# SCH_NSL-23-24_2023-12-20.net
KiCad netlist of a schematic drawn in EasyEDA
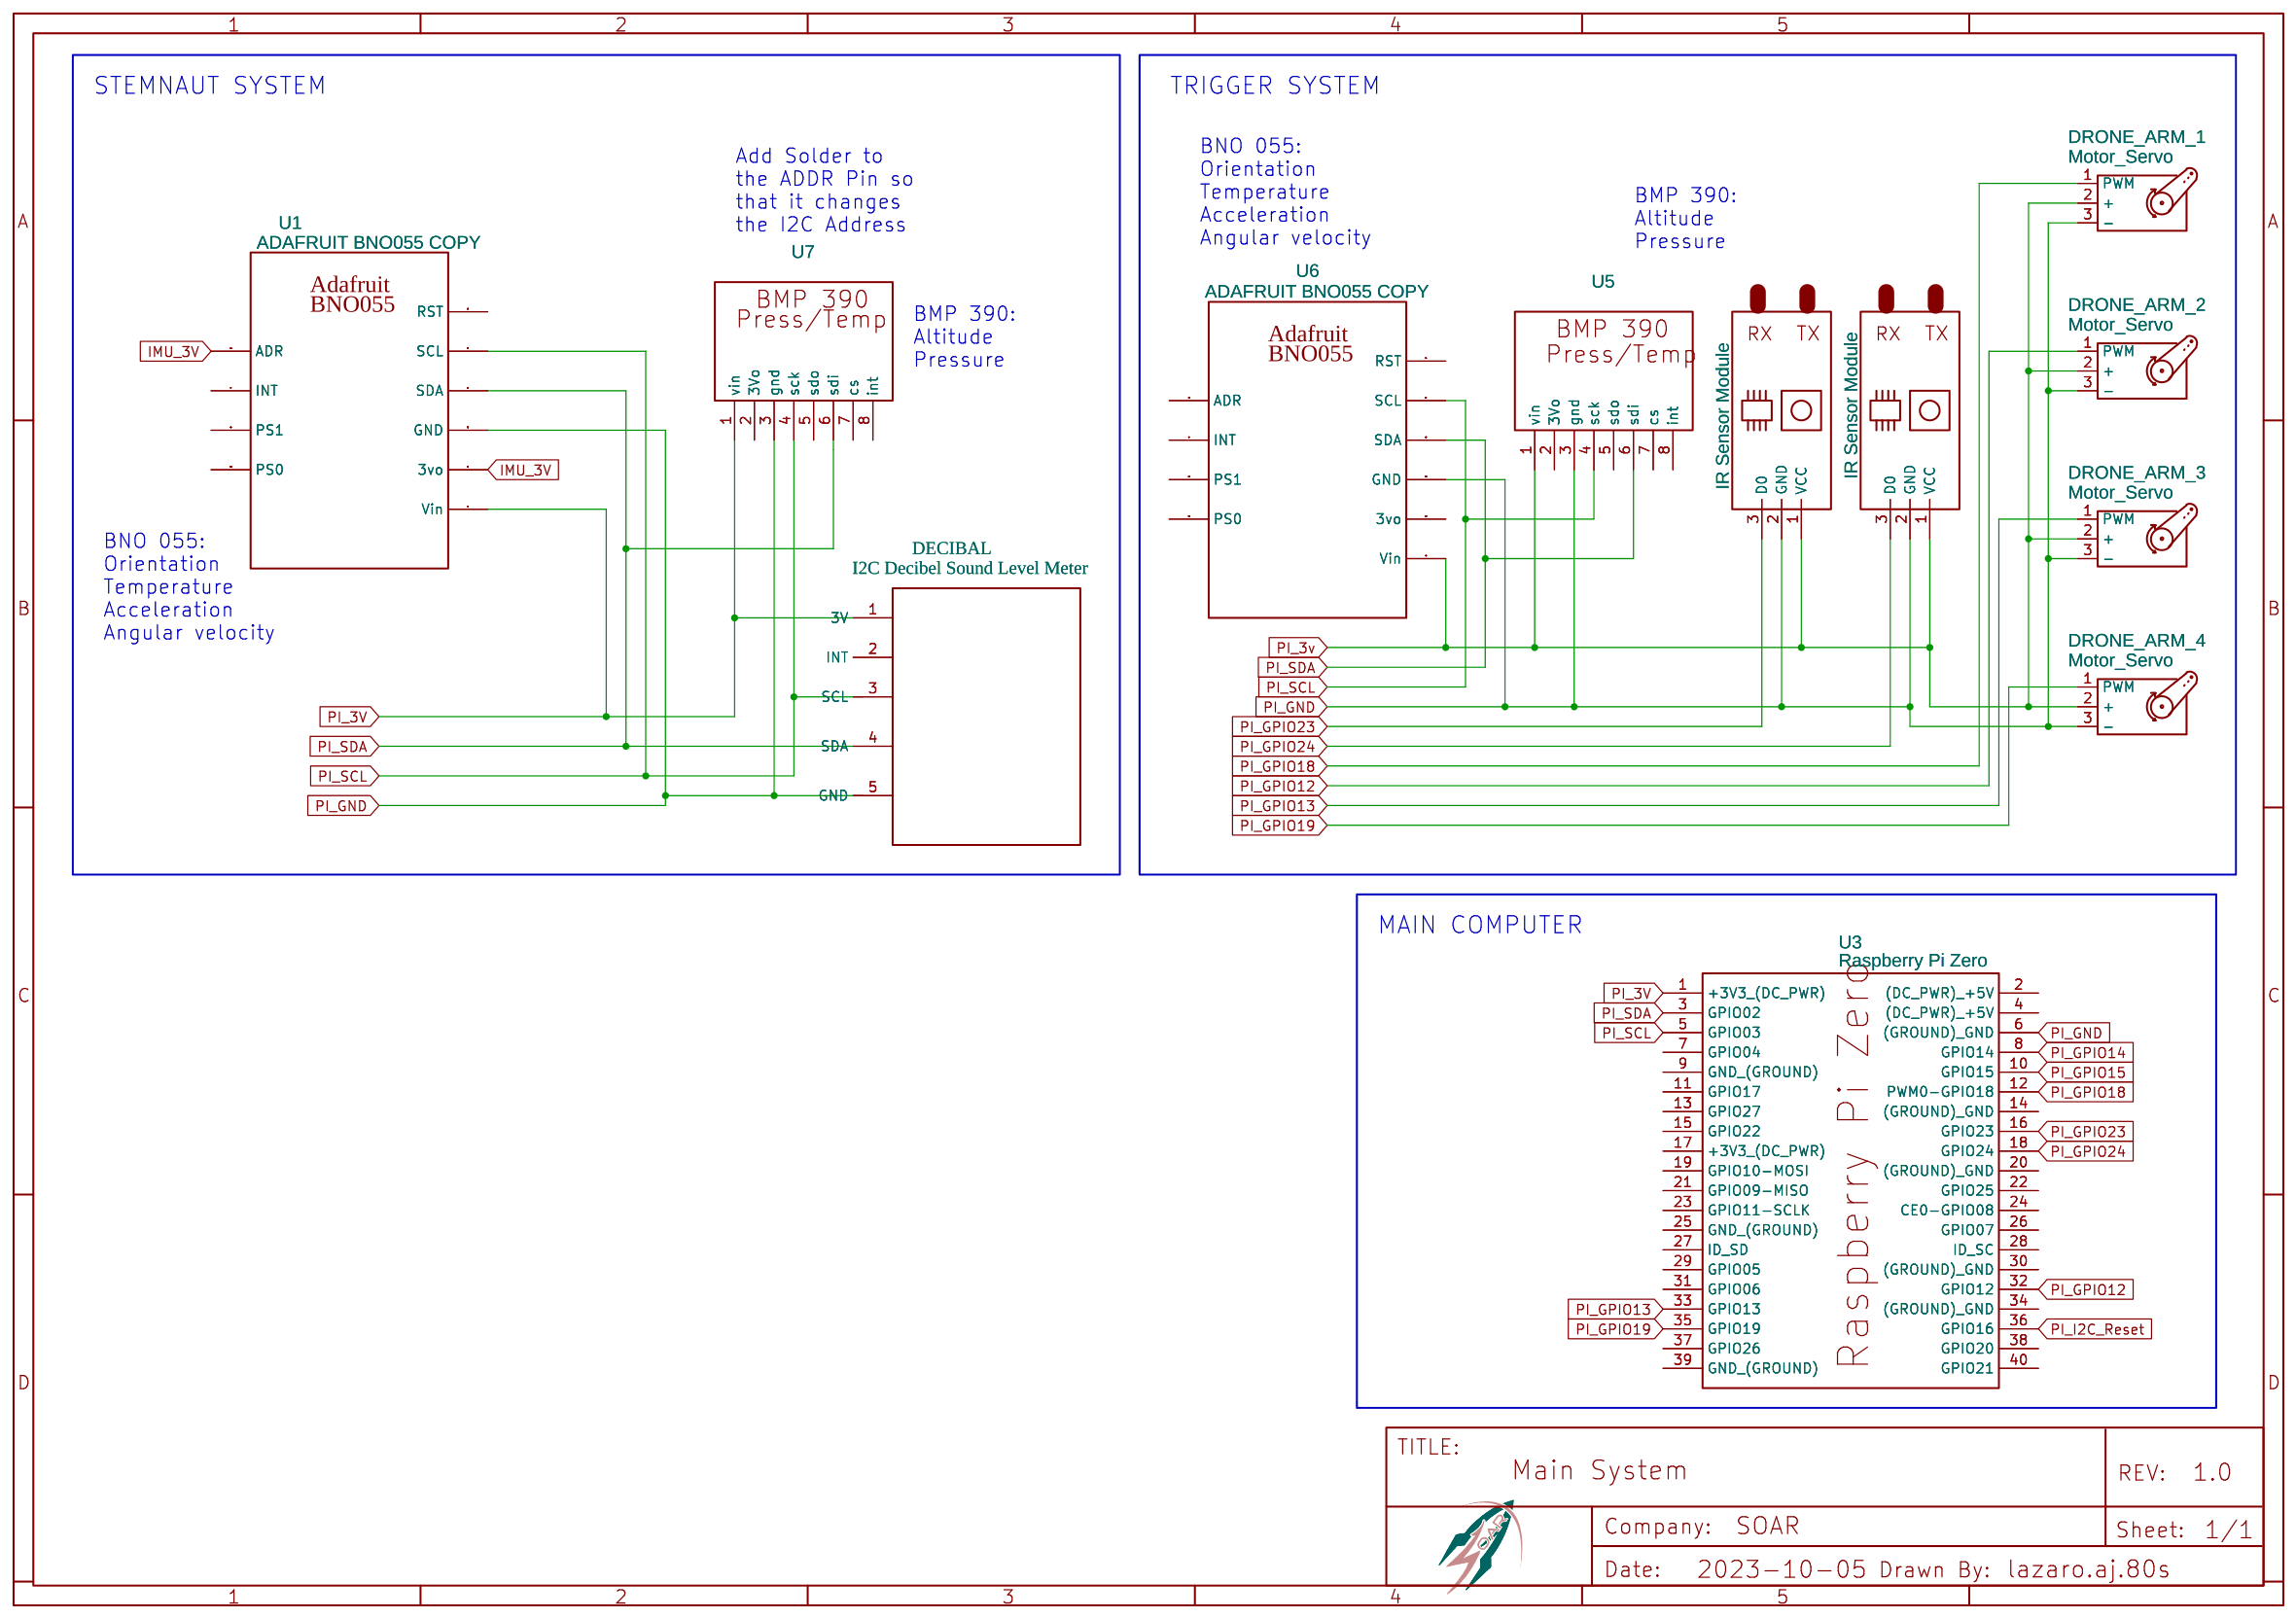
[diagram p0: Main System]
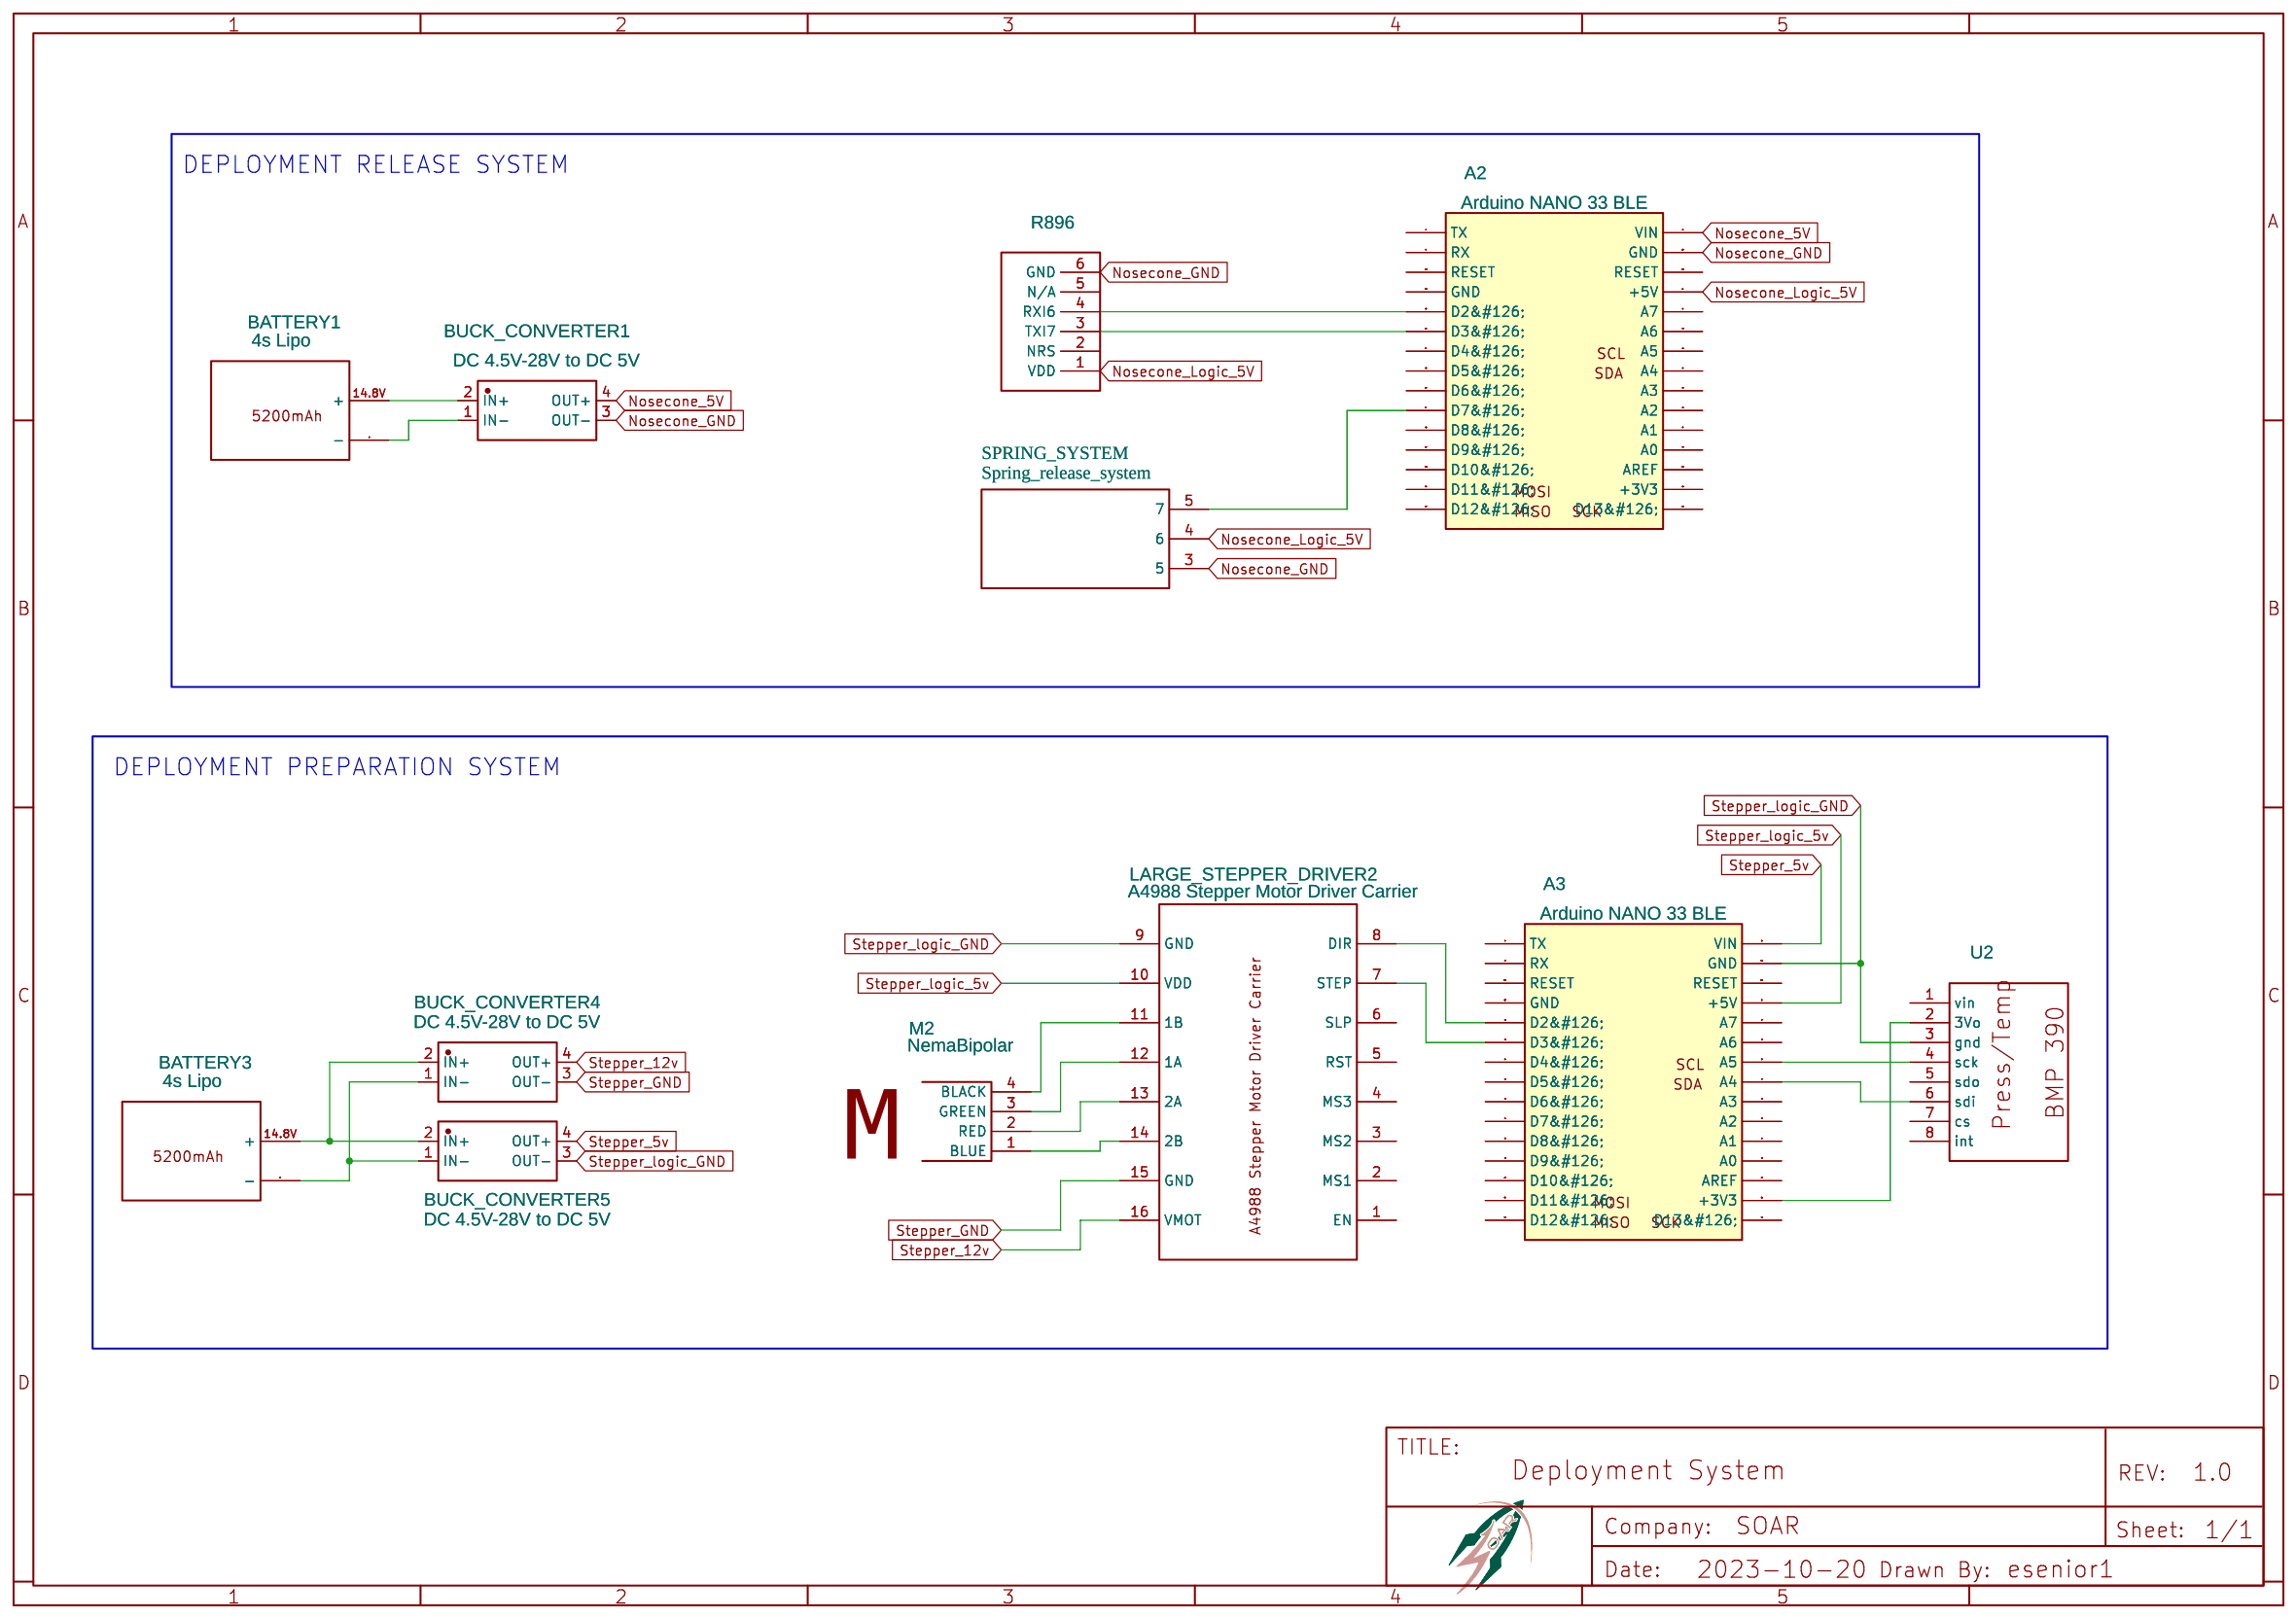
[diagram p1: Deployment System]
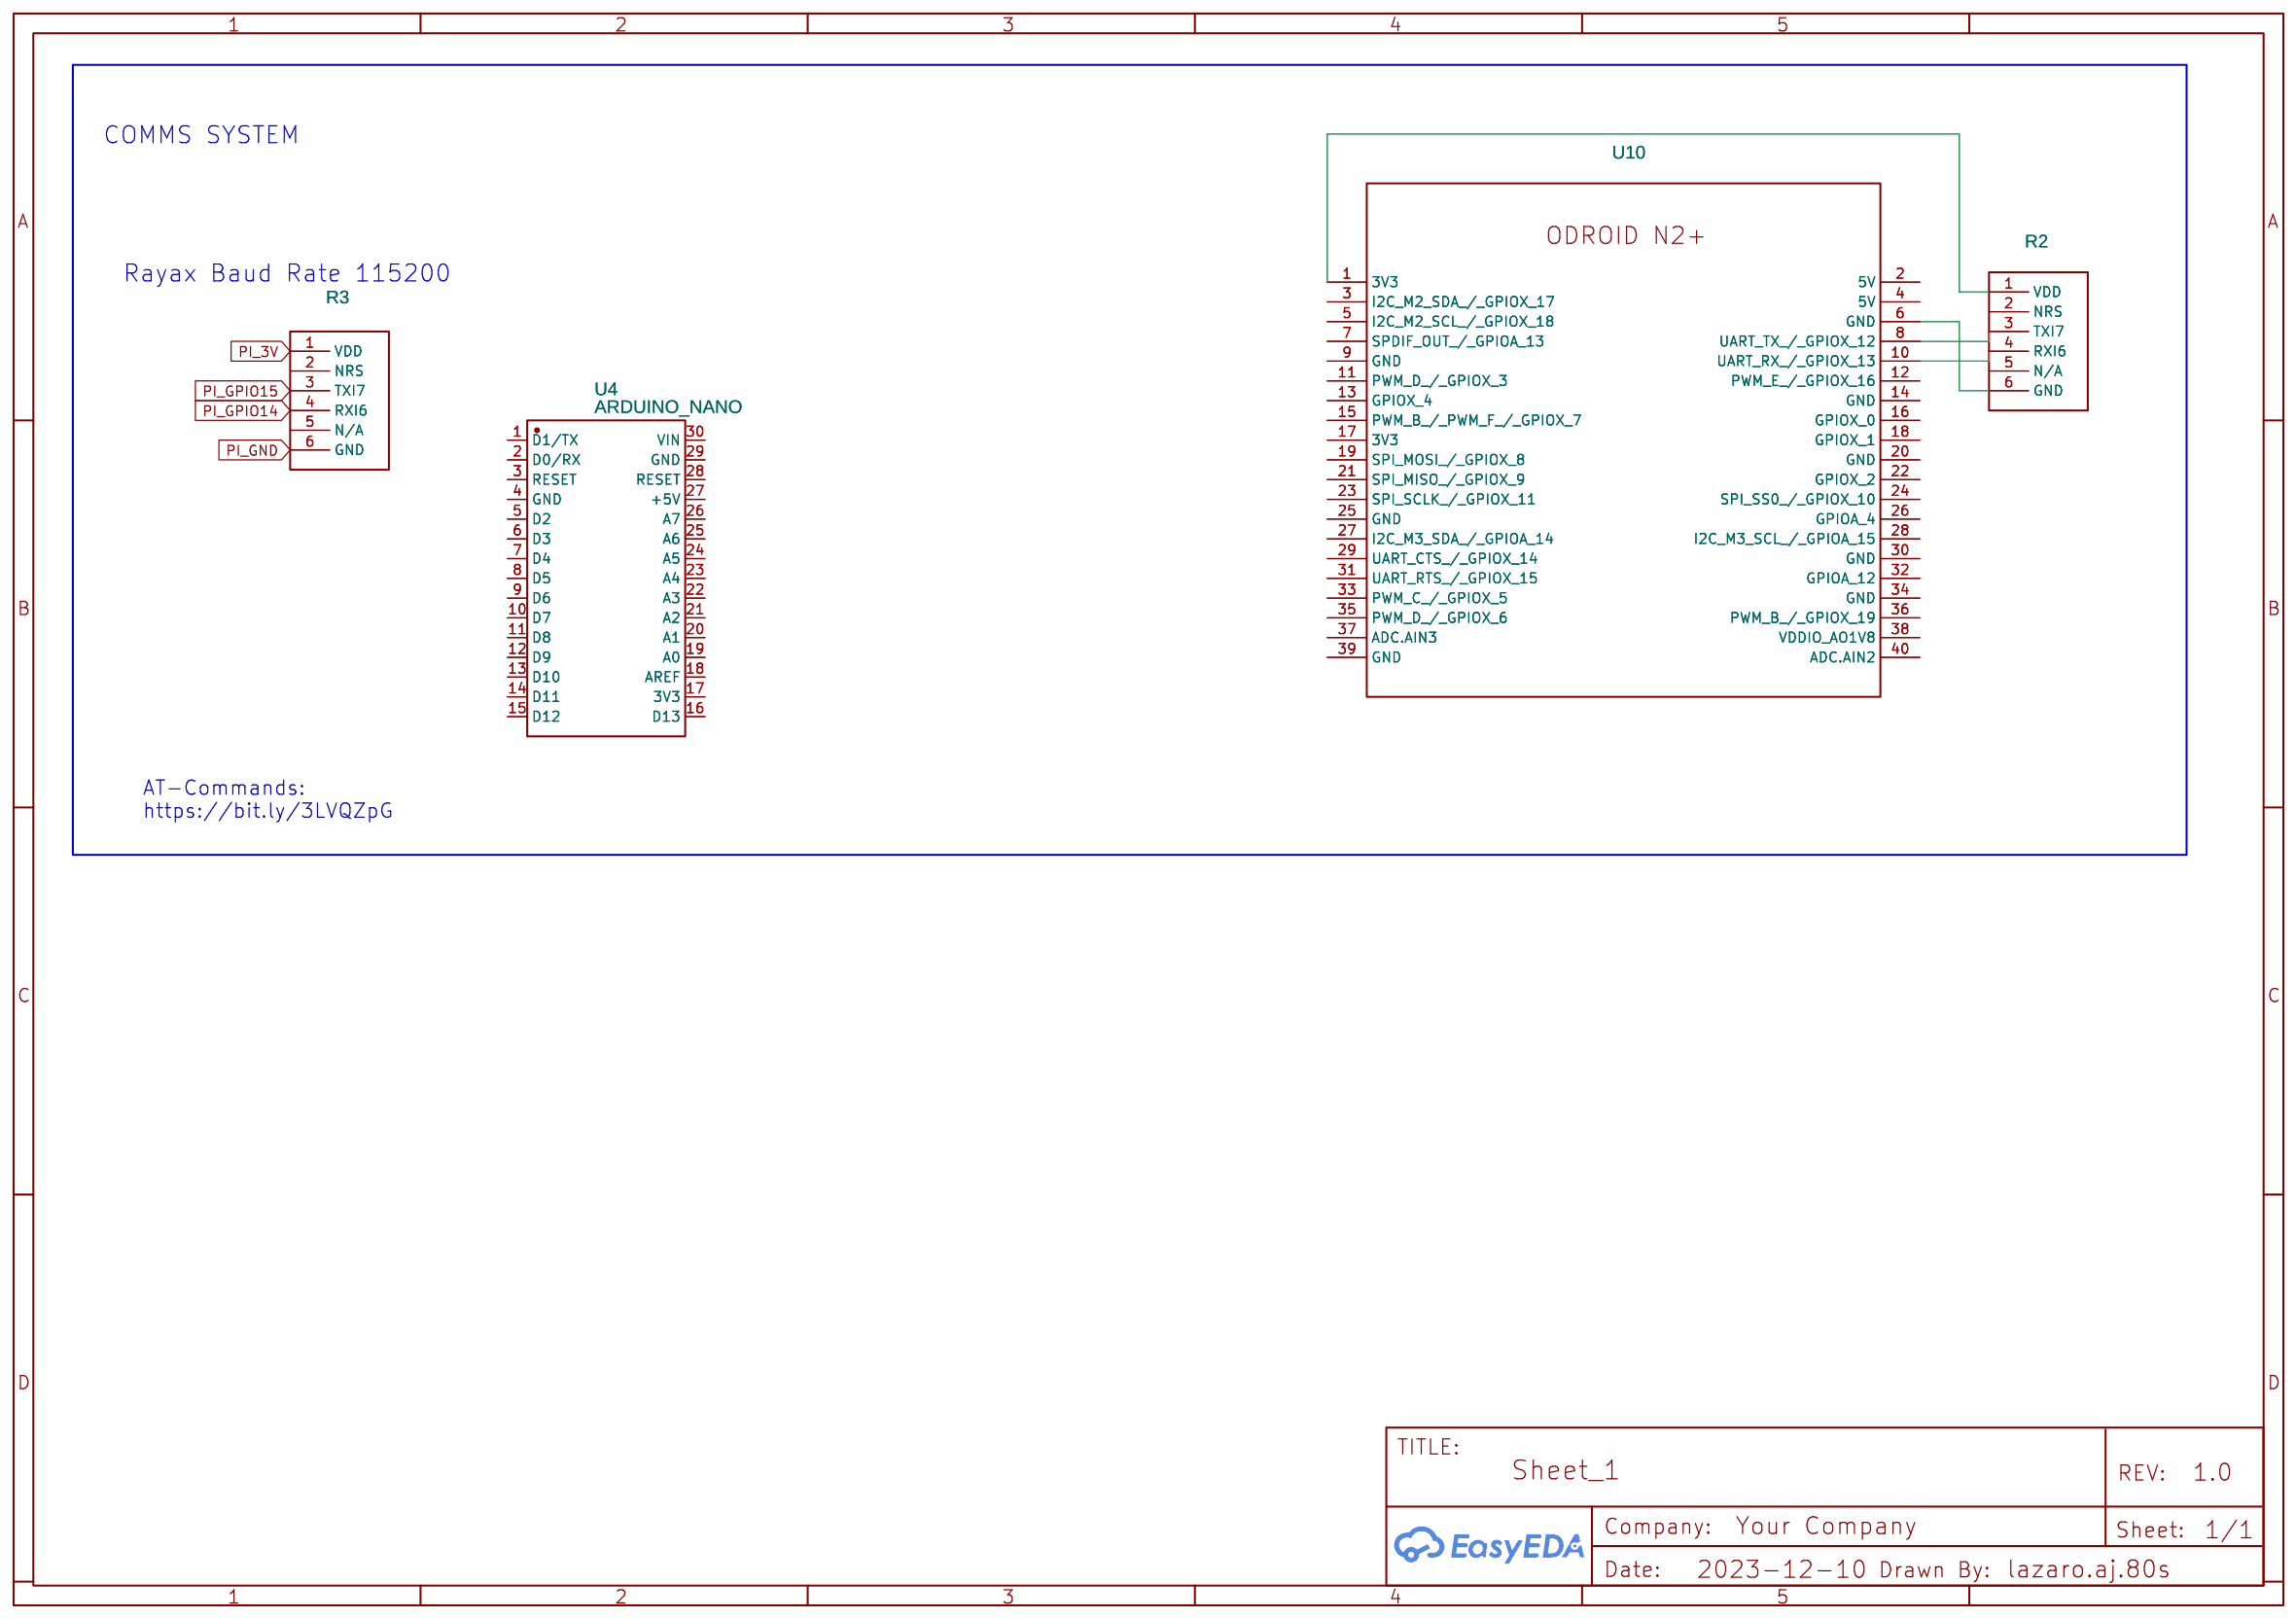
[diagram p2: Ground Computer]

(export (version "E")
  (design (tool "Eeschema 10.0.6"))
  (components
    (comp (ref "DECIBAL")
      (value "I2C Decibel Sound Level Meter")
      (libsource (lib "") (part "Unknown_485_-450"))
    )
    (comp (ref "DRONE_ARM_1") (value "Motor_Servo") (libsource (lib "") (part "Motor_Servo")))
    (comp (ref "DRONE_ARM_2") (value "Motor_Servo") (libsource (lib "") (part "Motor_Servo")))
    (comp (ref "DRONE_ARM_3") (value "Motor_Servo") (libsource (lib "") (part "Motor_Servo")))
    (comp (ref "DRONE_ARM_4") (value "Motor_Servo") (libsource (lib "") (part "Motor_Servo")))
    (comp (ref "NO2")
      (value "IR Sensor Module")
      (fields (field (name "Manufacturer Part") "Photosensitive Sensor Module"))
      (libsource (lib "") (part "IR Sensor Module - ElectroDino.com"))
    )
    (comp (ref "NO3")
      (value "IR Sensor Module")
      (fields (field (name "Manufacturer Part") "Photosensitive Sensor Module"))
      (libsource (lib "") (part "IR Sensor Module - ElectroDino.com"))
    )
    (comp (ref "U1")
      (value "ADAFRUIT BNO055 COPY")
      (fields (field (name "Manufacturer Part") "2472") (field (name "Manufacturer") "Adafruit"))
      (libsource (lib "") (part "ADAFRUIT BNO055 COPY"))
    )
    (comp (ref "U3") (value "Raspberry Pi Zero") (libsource (lib "") (part "Raspberry Pi Zero")))
    (comp (ref "U5")
      (value "NO")
      (fields (field (name "Manufacturer Part") "Adafruit"))
      (libsource (lib "") (part "BMP390 - BAROMETRIC PRESSURE AND ALTIMETER"))
    )
    (comp (ref "U6")
      (value "ADAFRUIT BNO055 COPY")
      (fields (field (name "Manufacturer Part") "2472") (field (name "Manufacturer") "Adafruit"))
      (libsource (lib "") (part "ADAFRUIT BNO055 COPY"))
    )
    (comp (ref "U7")
      (value "NO")
      (fields (field (name "Manufacturer Part") "Adafruit"))
      (libsource (lib "") (part "BMP390 - BAROMETRIC PRESSURE AND ALTIMETER_1"))
    )
    (comp (ref "A2") (value "Arduino NANO 33 BLE") (libsource (lib "") (part "Arduino NANO 33 BLE")))
    (comp (ref "A3") (value "Arduino NANO 33 BLE") (libsource (lib "") (part "Arduino NANO 33 BLE")))
    (comp (ref "BATTERY1") (value "4s Lipo") (libsource (lib "") (part "BateriaLiPo")))
    (comp (ref "BATTERY3") (value "4s Lipo") (libsource (lib "") (part "BateriaLiPo_1")))
    (comp (ref "BUCK_CONVERTER1")
      (value "DC 4.5V-28V to DC 5V")
      (fields (field (name "Manufacturer") "Senbeeda"))
      (libsource (lib "") (part "DC 4.5V-28V to DC 0.8V-20V"))
    )
    (comp (ref "BUCK_CONVERTER4")
      (value "DC 4.5V-28V to DC 5V")
      (fields (field (name "Manufacturer") "Senbeeda"))
      (libsource (lib "") (part "DC 4.5V-28V to DC 0.8V-20V"))
    )
    (comp (ref "BUCK_CONVERTER5")
      (value "DC 4.5V-28V to DC 5V")
      (fields (field (name "Manufacturer") "Senbeeda"))
      (libsource (lib "") (part "DC 4.5V-28V to DC 0.8V-20V"))
    )
    (comp (ref "LARGE_STEPPER_DRIVER2")
      (value "A4988 Stepper Motor Driver Carrier")
      (libsource (lib "") (part "A4988 Stepper Motor Driver Carrier"))
    )
    (comp (ref "M2") (value "NemaBipolar") (libsource (lib "") (part "NemaBipolar")))
    (comp (ref "R896") (value "NO") (libsource (lib "") (part "REYAX896")))
    (comp (ref "SPRING_SYSTEM")
      (value "Spring_release_system")
      (libsource (lib "") (part "Unknown_550_-540"))
    )
    (comp (ref "U2")
      (value "NO")
      (fields (field (name "Manufacturer Part") "Adafruit"))
      (libsource (lib "") (part "BMP390 - BAROMETRIC PRESSURE AND ALTIMETER"))
    )
    (comp (ref "R2") (value "NO") (libsource (lib "") (part "REYAX896")))
    (comp (ref "R3") (value "NO") (libsource (lib "") (part "REYAX896")))
    (comp (ref "U4") (value "ARDUINO_NANO") (libsource (lib "") (part "ARDUINO_NANO")))
    (comp (ref "U10") (value "NO") (libsource (lib "") (part "Odroid N2+")))
  )
  (nets
    (net (code "1") (name "IMU_3V") (class "Default")
      (node (ref "U1") (pin "3vo") (pinfunction "3vo_3vo") (pintype "unspecified"))
      (node (ref "U1") (pin "ADR") (pinfunction "ADR_ADR") (pintype "unspecified"))
    )
    (net (code "2") (name "Net-(A2-D2&#126;)") (class "Default")
      (node (ref "A2") (pin "D2") (pinfunction "D2&#126;_D2") (pintype "input"))
      (node (ref "R896") (pin "4") (pinfunction "RXI6_4") (pintype "passive"))
    )
    (net (code "3") (name "Net-(A2-D3&#126;)") (class "Default")
      (node (ref "A2") (pin "D3") (pinfunction "D3&#126;_D3") (pintype "input"))
      (node (ref "R896") (pin "3") (pinfunction "TXI7_3") (pintype "passive"))
    )
    (net (code "4") (name "Net-(A2-D7&#126;)") (class "Default")
      (node (ref "A2") (pin "D7") (pinfunction "D7&#126;_D7") (pintype "input"))
      (node (ref "SPRING_SYSTEM") (pin "5") (pinfunction "7_5") (pintype "unspecified"))
    )
    (net (code "5") (name "Net-(A3-+3V3)") (class "Default")
      (node (ref "A3") (pin "3V3") (pinfunction "+3V3_3V3") (pintype "input"))
      (node (ref "U2") (pin "2") (pinfunction "3Vo_2") (pintype "unspecified"))
    )
    (net (code "6") (name "Net-(A3-D2&#126;)") (class "Default")
      (node (ref "A3") (pin "D2") (pinfunction "D2&#126;_D2") (pintype "input"))
      (node (ref "LARGE_STEPPER_DRIVER2") (pin "8") (pinfunction "DIR_8") (pintype "unspecified"))
    )
    (net (code "7") (name "Net-(A3-D3&#126;)") (class "Default")
      (node (ref "A3") (pin "D3") (pinfunction "D3&#126;_D3") (pintype "input"))
      (node (ref "LARGE_STEPPER_DRIVER2") (pin "7") (pinfunction "STEP_7") (pintype "unspecified"))
    )
    (net (code "8") (name "Net-(BATTERY1-+)") (class "Default")
      (node (ref "BATTERY1") (pin "14.8V") (pinfunction "+_14.8V") (pintype "unspecified"))
      (node (ref "BUCK_CONVERTER1") (pin "2") (pinfunction "IN+_2") (pintype "unspecified"))
    )
    (net (code "9") (name "Net-(BATTERY1--)") (class "Default")
      (node (ref "BATTERY1") (pin "2") (pinfunction "-_2") (pintype "unspecified"))
      (node (ref "BUCK_CONVERTER1") (pin "1") (pinfunction "IN-_1") (pintype "unspecified"))
    )
    (net (code "10") (name "Net-(BATTERY3-+)") (class "Default")
      (node (ref "BATTERY3") (pin "14.8V") (pinfunction "+_14.8V") (pintype "unspecified"))
      (node (ref "BUCK_CONVERTER4") (pin "2") (pinfunction "IN+_2") (pintype "unspecified"))
      (node (ref "BUCK_CONVERTER5") (pin "2") (pinfunction "IN+_2") (pintype "unspecified"))
    )
    (net (code "11") (name "Net-(BATTERY3--)") (class "Default")
      (node (ref "BATTERY3") (pin "2") (pinfunction "-_2") (pintype "unspecified"))
      (node (ref "BUCK_CONVERTER4") (pin "1") (pinfunction "IN-_1") (pintype "unspecified"))
      (node (ref "BUCK_CONVERTER5") (pin "1") (pinfunction "IN-_1") (pintype "unspecified"))
    )
    (net (code "12") (name "Net-(LARGE_STEPPER_DRIVER2-1A)") (class "Default")
      (node (ref "LARGE_STEPPER_DRIVER2") (pin "12") (pinfunction "1A_12") (pintype "unspecified"))
      (node (ref "M2") (pin "3") (pinfunction "GREEN_3") (pintype "input"))
    )
    (net (code "13") (name "Net-(LARGE_STEPPER_DRIVER2-1B)") (class "Default")
      (node (ref "LARGE_STEPPER_DRIVER2") (pin "11") (pinfunction "1B_11") (pintype "unspecified"))
      (node (ref "M2") (pin "4") (pinfunction "BLACK_4") (pintype "input"))
    )
    (net (code "14") (name "Net-(LARGE_STEPPER_DRIVER2-2A)") (class "Default")
      (node (ref "LARGE_STEPPER_DRIVER2") (pin "13") (pinfunction "2A_13") (pintype "unspecified"))
      (node (ref "M2") (pin "2") (pinfunction "RED_2") (pintype "input"))
    )
    (net (code "15") (name "Net-(LARGE_STEPPER_DRIVER2-2B)") (class "Default")
      (node (ref "LARGE_STEPPER_DRIVER2") (pin "14") (pinfunction "2B_14") (pintype "unspecified"))
      (node (ref "M2") (pin "1") (pinfunction "BLUE_1") (pintype "input"))
    )
    (net (code "16") (name "Net-(R2-GND)") (class "Default")
      (node (ref "R2") (pin "6") (pinfunction "GND_6") (pintype "passive"))
      (node (ref "U10") (pin "6") (pinfunction "GND_6") (pintype "unspecified"))
    )
    (net (code "17") (name "Net-(R2-RXI6)") (class "Default")
      (node (ref "R2") (pin "4") (pinfunction "RXI6_4") (pintype "passive"))
      (node (ref "U10") (pin "10") (pinfunction "UART_RX_/_GPIOX_13_10") (pintype "unspecified"))
    )
    (net (code "18") (name "Net-(R2-TXI7)") (class "Default")
      (node (ref "R2") (pin "3") (pinfunction "TXI7_3") (pintype "passive"))
      (node (ref "U10") (pin "8") (pinfunction "UART_TX_/_GPIOX_12_8") (pintype "unspecified"))
    )
    (net (code "19") (name "Net-(R2-VDD)") (class "Default")
      (node (ref "R2") (pin "1") (pinfunction "VDD_1") (pintype "input"))
      (node (ref "U10") (pin "1") (pinfunction "3V3_1") (pintype "unspecified"))
    )
    (net (code "20") (name "Net-(U2-sck)") (class "Default")
      (node (ref "A3") (pin "A5") (pinfunction "A5_A5") (pintype "input"))
      (node (ref "U2") (pin "4") (pinfunction "sck_4") (pintype "unspecified"))
    )
    (net (code "21") (name "Net-(U2-sdi)") (class "Default")
      (node (ref "A3") (pin "A4") (pinfunction "A4_A4") (pintype "input"))
      (node (ref "U2") (pin "6") (pinfunction "sdi_6") (pintype "unspecified"))
    )
    (net (code "22") (name "Nosecone_5V") (class "Default")
      (node (ref "A2") (pin "VIN") (pinfunction "VIN_VIN") (pintype "input"))
      (node (ref "BUCK_CONVERTER1") (pin "4") (pinfunction "OUT+_4") (pintype "unspecified"))
    )
    (net (code "23") (name "Nosecone_GND") (class "Default")
      (node (ref "A2") (pin "GND1") (pinfunction "GND_GND1") (pintype "input"))
      (node (ref "BUCK_CONVERTER1") (pin "3") (pinfunction "OUT-_3") (pintype "unspecified"))
      (node (ref "R896") (pin "6") (pinfunction "GND_6") (pintype "passive"))
      (node (ref "SPRING_SYSTEM") (pin "3") (pinfunction "5_3") (pintype "unspecified"))
    )
    (net (code "24") (name "Nosecone_Logic_5V") (class "Default")
      (node (ref "A2") (pin "5V") (pinfunction "+5V_5V") (pintype "input"))
      (node (ref "R896") (pin "1") (pinfunction "VDD_1") (pintype "input"))
      (node (ref "SPRING_SYSTEM") (pin "4") (pinfunction "6_4") (pintype "unspecified"))
    )
    (net (code "25") (name "PI_3V") (class "Default")
      (node (ref "R3") (pin "1") (pinfunction "VDD_1") (pintype "input"))
      (node (ref "U1") (pin "Vin") (pinfunction "Vin_Vin") (pintype "unspecified"))
      (node (ref "U3") (pin "1") (pinfunction "+3V3_(DC_PWR)_1") (pintype "unspecified"))
      (node (ref "U7") (pin "1") (pinfunction "vin_1") (pintype "unspecified"))
    )
    (net (code "26") (name "PI_3v") (class "Default")
      (node (ref "DRONE_ARM_1") (pin "2") (pinfunction "+_2") (pintype "unspecified"))
      (node (ref "DRONE_ARM_2") (pin "2") (pinfunction "+_2") (pintype "unspecified"))
      (node (ref "DRONE_ARM_3") (pin "2") (pinfunction "+_2") (pintype "unspecified"))
      (node (ref "DRONE_ARM_4") (pin "2") (pinfunction "+_2") (pintype "unspecified"))
      (node (ref "NO2") (pin "1") (pinfunction "VCC_1") (pintype "unspecified"))
      (node (ref "NO3") (pin "1") (pinfunction "VCC_1") (pintype "unspecified"))
      (node (ref "U5") (pin "1") (pinfunction "vin_1") (pintype "unspecified"))
      (node (ref "U6") (pin "Vin") (pinfunction "Vin_Vin") (pintype "unspecified"))
    )
    (net (code "27") (name "PI_GND") (class "Default")
      (node (ref "DRONE_ARM_1") (pin "3") (pinfunction "-_3") (pintype "unspecified"))
      (node (ref "DRONE_ARM_2") (pin "3") (pinfunction "-_3") (pintype "unspecified"))
      (node (ref "DRONE_ARM_3") (pin "3") (pinfunction "-_3") (pintype "unspecified"))
      (node (ref "DRONE_ARM_4") (pin "3") (pinfunction "-_3") (pintype "unspecified"))
      (node (ref "NO2") (pin "2") (pinfunction "GND_2") (pintype "unspecified"))
      (node (ref "NO3") (pin "2") (pinfunction "GND_2") (pintype "unspecified"))
      (node (ref "R3") (pin "6") (pinfunction "GND_6") (pintype "passive"))
      (node (ref "U1") (pin "GND") (pinfunction "GND_GND") (pintype "unspecified"))
      (node (ref "U3") (pin "6") (pinfunction "(GROUND)_GND_6") (pintype "unspecified"))
      (node (ref "U5") (pin "3") (pinfunction "gnd_3") (pintype "unspecified"))
      (node (ref "U6") (pin "GND") (pinfunction "GND_GND") (pintype "unspecified"))
      (node (ref "U7") (pin "3") (pinfunction "gnd_3") (pintype "unspecified"))
    )
    (net (code "28") (name "PI_GPIO12") (class "Default")
      (node (ref "DRONE_ARM_2") (pin "1") (pinfunction "PWM_1") (pintype "unspecified"))
      (node (ref "U3") (pin "32") (pinfunction "GPIO12_32") (pintype "unspecified"))
    )
    (net (code "29") (name "PI_GPIO13") (class "Default")
      (node (ref "DRONE_ARM_3") (pin "1") (pinfunction "PWM_1") (pintype "unspecified"))
      (node (ref "U3") (pin "33") (pinfunction "GPIO13_33") (pintype "unspecified"))
    )
    (net (code "30") (name "PI_GPIO14") (class "Default")
      (node (ref "R3") (pin "4") (pinfunction "RXI6_4") (pintype "passive"))
      (node (ref "U3") (pin "8") (pinfunction "GPIO14_8") (pintype "unspecified"))
    )
    (net (code "31") (name "PI_GPIO15") (class "Default")
      (node (ref "R3") (pin "3") (pinfunction "TXI7_3") (pintype "passive"))
      (node (ref "U3") (pin "10") (pinfunction "GPIO15_10") (pintype "unspecified"))
    )
    (net (code "32") (name "PI_GPIO18") (class "Default")
      (node (ref "DRONE_ARM_1") (pin "1") (pinfunction "PWM_1") (pintype "unspecified"))
      (node (ref "U3") (pin "12") (pinfunction "PWM0-GPIO18_12") (pintype "unspecified"))
    )
    (net (code "33") (name "PI_GPIO19") (class "Default")
      (node (ref "DRONE_ARM_4") (pin "1") (pinfunction "PWM_1") (pintype "unspecified"))
      (node (ref "U3") (pin "35") (pinfunction "GPIO19_35") (pintype "unspecified"))
    )
    (net (code "34") (name "PI_GPIO23") (class "Default")
      (node (ref "NO3") (pin "3") (pinfunction "D0_3") (pintype "unspecified"))
      (node (ref "U3") (pin "16") (pinfunction "GPIO23_16") (pintype "unspecified"))
    )
    (net (code "35") (name "PI_GPIO24") (class "Default")
      (node (ref "NO2") (pin "3") (pinfunction "D0_3") (pintype "unspecified"))
      (node (ref "U3") (pin "18") (pinfunction "GPIO24_18") (pintype "unspecified"))
    )
    (net (code "36") (name "PI_I2C_Reset") (class "Default")
      (node (ref "U3") (pin "36") (pinfunction "GPIO16_36") (pintype "unspecified"))
    )
    (net (code "37") (name "PI_SCL") (class "Default")
      (node (ref "U1") (pin "SCL") (pinfunction "SCL_SCL") (pintype "unspecified"))
      (node (ref "U3") (pin "5") (pinfunction "GPIO03_5") (pintype "unspecified"))
      (node (ref "U5") (pin "4") (pinfunction "sck_4") (pintype "unspecified"))
      (node (ref "U6") (pin "SCL") (pinfunction "SCL_SCL") (pintype "unspecified"))
      (node (ref "U7") (pin "4") (pinfunction "sck_4") (pintype "unspecified"))
    )
    (net (code "38") (name "PI_SDA") (class "Default")
      (node (ref "U1") (pin "SDA") (pinfunction "SDA_SDA") (pintype "unspecified"))
      (node (ref "U3") (pin "3") (pinfunction "GPIO02_3") (pintype "unspecified"))
      (node (ref "U5") (pin "6") (pinfunction "sdi_6") (pintype "unspecified"))
      (node (ref "U6") (pin "SDA") (pinfunction "SDA_SDA") (pintype "unspecified"))
      (node (ref "U7") (pin "6") (pinfunction "sdi_6") (pintype "unspecified"))
    )
    (net (code "39") (name "Stepper_5v") (class "Default")
      (node (ref "A3") (pin "VIN") (pinfunction "VIN_VIN") (pintype "input"))
      (node (ref "BUCK_CONVERTER5") (pin "4") (pinfunction "OUT+_4") (pintype "unspecified"))
    )
    (net (code "40") (name "Stepper_12v") (class "Default")
      (node (ref "BUCK_CONVERTER4") (pin "4") (pinfunction "OUT+_4") (pintype "unspecified"))
      (node (ref "LARGE_STEPPER_DRIVER2") (pin "16") (pinfunction "VMOT_16") (pintype "unspecified"))
    )
    (net (code "41") (name "Stepper_GND") (class "Default")
      (node (ref "BUCK_CONVERTER4") (pin "3") (pinfunction "OUT-_3") (pintype "unspecified"))
      (node (ref "LARGE_STEPPER_DRIVER2") (pin "15") (pinfunction "GND_15") (pintype "unspecified"))
    )
    (net (code "42") (name "Stepper_logic_5v") (class "Default")
      (node (ref "A3") (pin "5V") (pinfunction "+5V_5V") (pintype "input"))
      (node (ref "LARGE_STEPPER_DRIVER2") (pin "10") (pinfunction "VDD_10") (pintype "unspecified"))
    )
    (net (code "43") (name "Stepper_logic_GND") (class "Default")
      (node (ref "A3") (pin "GND1") (pinfunction "GND_GND1") (pintype "input"))
      (node (ref "BUCK_CONVERTER5") (pin "3") (pinfunction "OUT-_3") (pintype "unspecified"))
      (node (ref "LARGE_STEPPER_DRIVER2") (pin "9") (pinfunction "GND_9") (pintype "unspecified"))
      (node (ref "U2") (pin "3") (pinfunction "gnd_3") (pintype "unspecified"))
    )
    (net (code "44") (name "unconnected-(A2-+3V3-Pad3V3)") (class "Default")
      (node (ref "A2") (pin "3V3") (pinfunction "+3V3_3V3") (pintype "input"))
    )
    (net (code "45") (name "unconnected-(A2-D4&#126;-PadD4)") (class "Default")
      (node (ref "A2") (pin "D4") (pinfunction "D4&#126;_D4") (pintype "input"))
    )
    (net (code "46") (name "unconnected-(A2-D5&#126;-PadD5)") (class "Default")
      (node (ref "A2") (pin "D5") (pinfunction "D5&#126;_D5") (pintype "input"))
    )
    (net (code "47") (name "unconnected-(A2-D6&#126;-PadD6)") (class "Default")
      (node (ref "A2") (pin "D6") (pinfunction "D6&#126;_D6") (pintype "input"))
    )
    (net (code "48") (name "unconnected-(A2-D8&#126;-PadD8)") (class "Default")
      (node (ref "A2") (pin "D8") (pinfunction "D8&#126;_D8") (pintype "input"))
    )
    (net (code "49") (name "unconnected-(A2-D9&#126;-PadD9)") (class "Default")
      (node (ref "A2") (pin "D9") (pinfunction "D9&#126;_D9") (pintype "input"))
    )
    (net (code "50") (name "unconnected-(A2-D10&#126;-PadD10)") (class "Default")
      (node (ref "A2") (pin "D10") (pinfunction "D10&#126;_D10") (pintype "input"))
    )
    (net (code "51") (name "unconnected-(A2-D11&#126;-PadD11)") (class "Default")
      (node (ref "A2") (pin "D11") (pinfunction "D11&#126;_D11") (pintype "input"))
    )
    (net (code "52") (name "unconnected-(A2-D12&#126;-PadD12)") (class "Default")
      (node (ref "A2") (pin "D12") (pinfunction "D12&#126;_D12") (pintype "input"))
    )
    (net (code "53") (name "unconnected-(A2-D13&#126;-PadD13)") (class "Default")
      (node (ref "A2") (pin "D13") (pinfunction "D13&#126;_D13") (pintype "input"))
    )
    (net (code "54") (name "unconnected-(A2-GND-PadGND2)") (class "Default")
      (node (ref "A2") (pin "GND2") (pinfunction "GND_GND2") (pintype "input"))
    )
    (net (code "55") (name "unconnected-(A2-PadA0)") (class "Default")
      (node (ref "A2") (pin "A0") (pinfunction "A0_A0") (pintype "input"))
    )
    (net (code "56") (name "unconnected-(A2-PadA1)") (class "Default")
      (node (ref "A2") (pin "A1") (pinfunction "A1_A1") (pintype "input"))
    )
    (net (code "57") (name "unconnected-(A2-PadA2)") (class "Default")
      (node (ref "A2") (pin "A2") (pinfunction "A2_A2") (pintype "input"))
    )
    (net (code "58") (name "unconnected-(A2-PadA3)") (class "Default")
      (node (ref "A2") (pin "A3") (pinfunction "A3_A3") (pintype "input"))
    )
    (net (code "59") (name "unconnected-(A2-PadA4)") (class "Default")
      (node (ref "A2") (pin "A4") (pinfunction "A4_A4") (pintype "input"))
    )
    (net (code "60") (name "unconnected-(A2-PadA5)") (class "Default")
      (node (ref "A2") (pin "A5") (pinfunction "A5_A5") (pintype "input"))
    )
    (net (code "61") (name "unconnected-(A2-PadA6)") (class "Default")
      (node (ref "A2") (pin "A6") (pinfunction "A6_A6") (pintype "input"))
    )
    (net (code "62") (name "unconnected-(A2-PadA7)") (class "Default")
      (node (ref "A2") (pin "A7") (pinfunction "A7_A7") (pintype "input"))
    )
    (net (code "63") (name "unconnected-(A2-PadAREF)") (class "Default")
      (node (ref "A2") (pin "AREF") (pinfunction "AREF_AREF") (pintype "input"))
    )
    (net (code "64") (name "unconnected-(A2-PadRX)") (class "Default")
      (node (ref "A2") (pin "RX") (pinfunction "RX_RX") (pintype "input"))
    )
    (net (code "65") (name "unconnected-(A2-PadTX)") (class "Default")
      (node (ref "A2") (pin "TX") (pinfunction "TX_TX") (pintype "input"))
    )
    (net (code "66") (name "unconnected-(A2-RESET-PadRESET1)") (class "Default")
      (node (ref "A2") (pin "RESET1") (pinfunction "RESET_RESET1") (pintype "input"))
    )
    (net (code "67") (name "unconnected-(A2-RESET-PadRESET2)") (class "Default")
      (node (ref "A2") (pin "RESET2") (pinfunction "RESET_RESET2") (pintype "input"))
    )
    (net (code "68") (name "unconnected-(A3-D4&#126;-PadD4)") (class "Default")
      (node (ref "A3") (pin "D4") (pinfunction "D4&#126;_D4") (pintype "input"))
    )
    (net (code "69") (name "unconnected-(A3-D5&#126;-PadD5)") (class "Default")
      (node (ref "A3") (pin "D5") (pinfunction "D5&#126;_D5") (pintype "input"))
    )
    (net (code "70") (name "unconnected-(A3-D6&#126;-PadD6)") (class "Default")
      (node (ref "A3") (pin "D6") (pinfunction "D6&#126;_D6") (pintype "input"))
    )
    (net (code "71") (name "unconnected-(A3-D7&#126;-PadD7)") (class "Default")
      (node (ref "A3") (pin "D7") (pinfunction "D7&#126;_D7") (pintype "input"))
    )
    (net (code "72") (name "unconnected-(A3-D8&#126;-PadD8)") (class "Default")
      (node (ref "A3") (pin "D8") (pinfunction "D8&#126;_D8") (pintype "input"))
    )
    (net (code "73") (name "unconnected-(A3-D9&#126;-PadD9)") (class "Default")
      (node (ref "A3") (pin "D9") (pinfunction "D9&#126;_D9") (pintype "input"))
    )
    (net (code "74") (name "unconnected-(A3-D10&#126;-PadD10)") (class "Default")
      (node (ref "A3") (pin "D10") (pinfunction "D10&#126;_D10") (pintype "input"))
    )
    (net (code "75") (name "unconnected-(A3-D11&#126;-PadD11)") (class "Default")
      (node (ref "A3") (pin "D11") (pinfunction "D11&#126;_D11") (pintype "input"))
    )
    (net (code "76") (name "unconnected-(A3-D12&#126;-PadD12)") (class "Default")
      (node (ref "A3") (pin "D12") (pinfunction "D12&#126;_D12") (pintype "input"))
    )
    (net (code "77") (name "unconnected-(A3-D13&#126;-PadD13)") (class "Default")
      (node (ref "A3") (pin "D13") (pinfunction "D13&#126;_D13") (pintype "input"))
    )
    (net (code "78") (name "unconnected-(A3-GND-PadGND2)") (class "Default")
      (node (ref "A3") (pin "GND2") (pinfunction "GND_GND2") (pintype "input"))
    )
    (net (code "79") (name "unconnected-(A3-PadA0)") (class "Default")
      (node (ref "A3") (pin "A0") (pinfunction "A0_A0") (pintype "input"))
    )
    (net (code "80") (name "unconnected-(A3-PadA1)") (class "Default")
      (node (ref "A3") (pin "A1") (pinfunction "A1_A1") (pintype "input"))
    )
    (net (code "81") (name "unconnected-(A3-PadA2)") (class "Default")
      (node (ref "A3") (pin "A2") (pinfunction "A2_A2") (pintype "input"))
    )
    (net (code "82") (name "unconnected-(A3-PadA3)") (class "Default")
      (node (ref "A3") (pin "A3") (pinfunction "A3_A3") (pintype "input"))
    )
    (net (code "83") (name "unconnected-(A3-PadA6)") (class "Default")
      (node (ref "A3") (pin "A6") (pinfunction "A6_A6") (pintype "input"))
    )
    (net (code "84") (name "unconnected-(A3-PadA7)") (class "Default")
      (node (ref "A3") (pin "A7") (pinfunction "A7_A7") (pintype "input"))
    )
    (net (code "85") (name "unconnected-(A3-PadAREF)") (class "Default")
      (node (ref "A3") (pin "AREF") (pinfunction "AREF_AREF") (pintype "input"))
    )
    (net (code "86") (name "unconnected-(A3-PadRX)") (class "Default")
      (node (ref "A3") (pin "RX") (pinfunction "RX_RX") (pintype "input"))
    )
    (net (code "87") (name "unconnected-(A3-PadTX)") (class "Default")
      (node (ref "A3") (pin "TX") (pinfunction "TX_TX") (pintype "input"))
    )
    (net (code "88") (name "unconnected-(A3-RESET-PadRESET1)") (class "Default")
      (node (ref "A3") (pin "RESET1") (pinfunction "RESET_RESET1") (pintype "input"))
    )
    (net (code "89") (name "unconnected-(A3-RESET-PadRESET2)") (class "Default")
      (node (ref "A3") (pin "RESET2") (pinfunction "RESET_RESET2") (pintype "input"))
    )
    (net (code "90") (name "unconnected-(DECIBAL-3V-Pad1)") (class "Default")
      (node (ref "DECIBAL") (pin "1") (pinfunction "3V_1") (pintype "unspecified"))
    )
    (net (code "91") (name "unconnected-(DECIBAL-GND-Pad5)") (class "Default")
      (node (ref "DECIBAL") (pin "5") (pinfunction "GND_5") (pintype "unspecified"))
    )
    (net (code "92") (name "unconnected-(DECIBAL-INT-Pad2)") (class "Default")
      (node (ref "DECIBAL") (pin "2") (pinfunction "INT_2") (pintype "unspecified"))
    )
    (net (code "93") (name "unconnected-(DECIBAL-SCL-Pad3)") (class "Default")
      (node (ref "DECIBAL") (pin "3") (pinfunction "SCL_3") (pintype "unspecified"))
    )
    (net (code "94") (name "unconnected-(DECIBAL-SDA-Pad4)") (class "Default")
      (node (ref "DECIBAL") (pin "4") (pinfunction "SDA_4") (pintype "unspecified"))
    )
    (net (code "95") (name "unconnected-(LARGE_STEPPER_DRIVER2-EN-Pad1)") (class "Default")
      (node (ref "LARGE_STEPPER_DRIVER2") (pin "1") (pinfunction "EN_1") (pintype "unspecified"))
    )
    (net (code "96") (name "unconnected-(LARGE_STEPPER_DRIVER2-MS1-Pad2)") (class "Default")
      (node (ref "LARGE_STEPPER_DRIVER2") (pin "2") (pinfunction "MS1_2") (pintype "unspecified"))
    )
    (net (code "97") (name "unconnected-(LARGE_STEPPER_DRIVER2-MS2-Pad3)") (class "Default")
      (node (ref "LARGE_STEPPER_DRIVER2") (pin "3") (pinfunction "MS2_3") (pintype "unspecified"))
    )
    (net (code "98") (name "unconnected-(LARGE_STEPPER_DRIVER2-MS3-Pad4)") (class "Default")
      (node (ref "LARGE_STEPPER_DRIVER2") (pin "4") (pinfunction "MS3_4") (pintype "unspecified"))
    )
    (net (code "99") (name "unconnected-(LARGE_STEPPER_DRIVER2-RST-Pad5)") (class "Default")
      (node (ref "LARGE_STEPPER_DRIVER2") (pin "5") (pinfunction "RST_5") (pintype "unspecified"))
    )
    (net (code "100") (name "unconnected-(LARGE_STEPPER_DRIVER2-SLP-Pad6)") (class "Default")
      (node (ref "LARGE_STEPPER_DRIVER2") (pin "6") (pinfunction "SLP_6") (pintype "unspecified"))
    )
    (net (code "101") (name "unconnected-(R2-NRS-Pad2)") (class "Default")
      (node (ref "R2") (pin "2") (pinfunction "NRS_2") (pintype "input"))
    )
    (net (code "102") (name "unconnected-(R2-N{slash}A-Pad5)") (class "Default")
      (node (ref "R2") (pin "5") (pinfunction "N/A_5") (pintype "passive"))
    )
    (net (code "103") (name "unconnected-(R3-NRS-Pad2)") (class "Default")
      (node (ref "R3") (pin "2") (pinfunction "NRS_2") (pintype "input"))
    )
    (net (code "104") (name "unconnected-(R3-N{slash}A-Pad5)") (class "Default")
      (node (ref "R3") (pin "5") (pinfunction "N/A_5") (pintype "passive"))
    )
    (net (code "105") (name "unconnected-(R896-NRS-Pad2)") (class "Default")
      (node (ref "R896") (pin "2") (pinfunction "NRS_2") (pintype "input"))
    )
    (net (code "106") (name "unconnected-(R896-N{slash}A-Pad5)") (class "Default")
      (node (ref "R896") (pin "5") (pinfunction "N/A_5") (pintype "passive"))
    )
    (net (code "107") (name "unconnected-(U1-PadINT)") (class "Default")
      (node (ref "U1") (pin "INT") (pinfunction "INT_INT") (pintype "unspecified"))
    )
    (net (code "108") (name "unconnected-(U1-PadPS0)") (class "Default")
      (node (ref "U1") (pin "PS0") (pinfunction "PS0_PS0") (pintype "unspecified"))
    )
    (net (code "109") (name "unconnected-(U1-PadPS1)") (class "Default")
      (node (ref "U1") (pin "PS1") (pinfunction "PS1_PS1") (pintype "unspecified"))
    )
    (net (code "110") (name "unconnected-(U1-PadRST)") (class "Default")
      (node (ref "U1") (pin "RST") (pinfunction "RST_RST") (pintype "unspecified"))
    )
    (net (code "111") (name "unconnected-(U2-cs-Pad7)") (class "Default")
      (node (ref "U2") (pin "7") (pinfunction "cs_7") (pintype "unspecified"))
    )
    (net (code "112") (name "unconnected-(U2-int-Pad8)") (class "Default")
      (node (ref "U2") (pin "8") (pinfunction "int_8") (pintype "unspecified"))
    )
    (net (code "113") (name "unconnected-(U2-sdo-Pad5)") (class "Default")
      (node (ref "U2") (pin "5") (pinfunction "sdo_5") (pintype "unspecified"))
    )
    (net (code "114") (name "unconnected-(U2-vin-Pad1)") (class "Default")
      (node (ref "U2") (pin "1") (pinfunction "vin_1") (pintype "unspecified"))
    )
    (net (code "115") (name "unconnected-(U3-(DC_PWR)_+5V-Pad2)") (class "Default")
      (node (ref "U3") (pin "2") (pinfunction "(DC_PWR)_+5V_2") (pintype "unspecified"))
    )
    (net (code "116") (name "unconnected-(U3-(DC_PWR)_+5V-Pad4)") (class "Default")
      (node (ref "U3") (pin "4") (pinfunction "(DC_PWR)_+5V_4") (pintype "unspecified"))
    )
    (net (code "117") (name "unconnected-(U3-(GROUND)_GND-Pad14)") (class "Default")
      (node (ref "U3") (pin "14") (pinfunction "(GROUND)_GND_14") (pintype "unspecified"))
    )
    (net (code "118") (name "unconnected-(U3-(GROUND)_GND-Pad20)") (class "Default")
      (node (ref "U3") (pin "20") (pinfunction "(GROUND)_GND_20") (pintype "unspecified"))
    )
    (net (code "119") (name "unconnected-(U3-(GROUND)_GND-Pad30)") (class "Default")
      (node (ref "U3") (pin "30") (pinfunction "(GROUND)_GND_30") (pintype "unspecified"))
    )
    (net (code "120") (name "unconnected-(U3-(GROUND)_GND-Pad34)") (class "Default")
      (node (ref "U3") (pin "34") (pinfunction "(GROUND)_GND_34") (pintype "unspecified"))
    )
    (net (code "121") (name "unconnected-(U3-+3V3_(DC_PWR)-Pad17)") (class "Default")
      (node (ref "U3") (pin "17") (pinfunction "+3V3_(DC_PWR)_17") (pintype "unspecified"))
    )
    (net (code "122") (name "unconnected-(U3-CE0-GPIO08-Pad24)") (class "Default")
      (node (ref "U3") (pin "24") (pinfunction "CE0-GPIO08_24") (pintype "unspecified"))
    )
    (net (code "123") (name "unconnected-(U3-GND_(GROUND)-Pad9)") (class "Default")
      (node (ref "U3") (pin "9") (pinfunction "GND_(GROUND)_9") (pintype "unspecified"))
    )
    (net (code "124") (name "unconnected-(U3-GND_(GROUND)-Pad25)") (class "Default")
      (node (ref "U3") (pin "25") (pinfunction "GND_(GROUND)_25") (pintype "unspecified"))
    )
    (net (code "125") (name "unconnected-(U3-GND_(GROUND)-Pad39)") (class "Default")
      (node (ref "U3") (pin "39") (pinfunction "GND_(GROUND)_39") (pintype "unspecified"))
    )
    (net (code "126") (name "unconnected-(U3-GPIO04-Pad7)") (class "Default")
      (node (ref "U3") (pin "7") (pinfunction "GPIO04_7") (pintype "unspecified"))
    )
    (net (code "127") (name "unconnected-(U3-GPIO05-Pad29)") (class "Default")
      (node (ref "U3") (pin "29") (pinfunction "GPIO05_29") (pintype "unspecified"))
    )
    (net (code "128") (name "unconnected-(U3-GPIO06-Pad31)") (class "Default")
      (node (ref "U3") (pin "31") (pinfunction "GPIO06_31") (pintype "unspecified"))
    )
    (net (code "129") (name "unconnected-(U3-GPIO07-Pad26)") (class "Default")
      (node (ref "U3") (pin "26") (pinfunction "GPIO07_26") (pintype "unspecified"))
    )
    (net (code "130") (name "unconnected-(U3-GPIO09-MISO-Pad21)") (class "Default")
      (node (ref "U3") (pin "21") (pinfunction "GPIO09-MISO_21") (pintype "unspecified"))
    )
    (net (code "131") (name "unconnected-(U3-GPIO10-MOSI-Pad19)") (class "Default")
      (node (ref "U3") (pin "19") (pinfunction "GPIO10-MOSI_19") (pintype "unspecified"))
    )
    (net (code "132") (name "unconnected-(U3-GPIO11-SCLK-Pad23)") (class "Default")
      (node (ref "U3") (pin "23") (pinfunction "GPIO11-SCLK_23") (pintype "unspecified"))
    )
    (net (code "133") (name "unconnected-(U3-GPIO17-Pad11)") (class "Default")
      (node (ref "U3") (pin "11") (pinfunction "GPIO17_11") (pintype "unspecified"))
    )
    (net (code "134") (name "unconnected-(U3-GPIO20-Pad38)") (class "Default")
      (node (ref "U3") (pin "38") (pinfunction "GPIO20_38") (pintype "unspecified"))
    )
    (net (code "135") (name "unconnected-(U3-GPIO21-Pad40)") (class "Default")
      (node (ref "U3") (pin "40") (pinfunction "GPIO21_40") (pintype "unspecified"))
    )
    (net (code "136") (name "unconnected-(U3-GPIO22-Pad15)") (class "Default")
      (node (ref "U3") (pin "15") (pinfunction "GPIO22_15") (pintype "unspecified"))
    )
    (net (code "137") (name "unconnected-(U3-GPIO25-Pad22)") (class "Default")
      (node (ref "U3") (pin "22") (pinfunction "GPIO25_22") (pintype "unspecified"))
    )
    (net (code "138") (name "unconnected-(U3-GPIO26-Pad37)") (class "Default")
      (node (ref "U3") (pin "37") (pinfunction "GPIO26_37") (pintype "unspecified"))
    )
    (net (code "139") (name "unconnected-(U3-GPIO27-Pad13)") (class "Default")
      (node (ref "U3") (pin "13") (pinfunction "GPIO27_13") (pintype "unspecified"))
    )
    (net (code "140") (name "unconnected-(U3-ID_SC-Pad28)") (class "Default")
      (node (ref "U3") (pin "28") (pinfunction "ID_SC_28") (pintype "unspecified"))
    )
    (net (code "141") (name "unconnected-(U3-ID_SD-Pad27)") (class "Default")
      (node (ref "U3") (pin "27") (pinfunction "ID_SD_27") (pintype "unspecified"))
    )
    (net (code "142") (name "unconnected-(U4-+5V-Pad27)") (class "Default")
      (node (ref "U4") (pin "27") (pinfunction "+5V_27") (pintype "unspecified"))
    )
    (net (code "143") (name "unconnected-(U4-3V3-Pad17)") (class "Default")
      (node (ref "U4") (pin "17") (pinfunction "3V3_17") (pintype "unspecified"))
    )
    (net (code "144") (name "unconnected-(U4-A0-Pad19)") (class "Default")
      (node (ref "U4") (pin "19") (pinfunction "A0_19") (pintype "unspecified"))
    )
    (net (code "145") (name "unconnected-(U4-A1-Pad20)") (class "Default")
      (node (ref "U4") (pin "20") (pinfunction "A1_20") (pintype "unspecified"))
    )
    (net (code "146") (name "unconnected-(U4-A2-Pad21)") (class "Default")
      (node (ref "U4") (pin "21") (pinfunction "A2_21") (pintype "unspecified"))
    )
    (net (code "147") (name "unconnected-(U4-A3-Pad22)") (class "Default")
      (node (ref "U4") (pin "22") (pinfunction "A3_22") (pintype "unspecified"))
    )
    (net (code "148") (name "unconnected-(U4-A4-Pad23)") (class "Default")
      (node (ref "U4") (pin "23") (pinfunction "A4_23") (pintype "unspecified"))
    )
    (net (code "149") (name "unconnected-(U4-A5-Pad24)") (class "Default")
      (node (ref "U4") (pin "24") (pinfunction "A5_24") (pintype "unspecified"))
    )
    (net (code "150") (name "unconnected-(U4-A6-Pad25)") (class "Default")
      (node (ref "U4") (pin "25") (pinfunction "A6_25") (pintype "unspecified"))
    )
    (net (code "151") (name "unconnected-(U4-A7-Pad26)") (class "Default")
      (node (ref "U4") (pin "26") (pinfunction "A7_26") (pintype "unspecified"))
    )
    (net (code "152") (name "unconnected-(U4-AREF-Pad18)") (class "Default")
      (node (ref "U4") (pin "18") (pinfunction "AREF_18") (pintype "unspecified"))
    )
    (net (code "153") (name "unconnected-(U4-D0{slash}RX-Pad2)") (class "Default")
      (node (ref "U4") (pin "2") (pinfunction "D0/RX_2") (pintype "unspecified"))
    )
    (net (code "154") (name "unconnected-(U4-D1{slash}TX-Pad1)") (class "Default")
      (node (ref "U4") (pin "1") (pinfunction "D1/TX_1") (pintype "unspecified"))
    )
    (net (code "155") (name "unconnected-(U4-D2-Pad5)") (class "Default")
      (node (ref "U4") (pin "5") (pinfunction "D2_5") (pintype "unspecified"))
    )
    (net (code "156") (name "unconnected-(U4-D3-Pad6)") (class "Default")
      (node (ref "U4") (pin "6") (pinfunction "D3_6") (pintype "unspecified"))
    )
    (net (code "157") (name "unconnected-(U4-D4-Pad7)") (class "Default")
      (node (ref "U4") (pin "7") (pinfunction "D4_7") (pintype "unspecified"))
    )
    (net (code "158") (name "unconnected-(U4-D5-Pad8)") (class "Default")
      (node (ref "U4") (pin "8") (pinfunction "D5_8") (pintype "unspecified"))
    )
    (net (code "159") (name "unconnected-(U4-D6-Pad9)") (class "Default")
      (node (ref "U4") (pin "9") (pinfunction "D6_9") (pintype "unspecified"))
    )
    (net (code "160") (name "unconnected-(U4-D7-Pad10)") (class "Default")
      (node (ref "U4") (pin "10") (pinfunction "D7_10") (pintype "unspecified"))
    )
    (net (code "161") (name "unconnected-(U4-D8-Pad11)") (class "Default")
      (node (ref "U4") (pin "11") (pinfunction "D8_11") (pintype "unspecified"))
    )
    (net (code "162") (name "unconnected-(U4-D9-Pad12)") (class "Default")
      (node (ref "U4") (pin "12") (pinfunction "D9_12") (pintype "unspecified"))
    )
    (net (code "163") (name "unconnected-(U4-D10-Pad13)") (class "Default")
      (node (ref "U4") (pin "13") (pinfunction "D10_13") (pintype "unspecified"))
    )
    (net (code "164") (name "unconnected-(U4-D11-Pad14)") (class "Default")
      (node (ref "U4") (pin "14") (pinfunction "D11_14") (pintype "unspecified"))
    )
    (net (code "165") (name "unconnected-(U4-D12-Pad15)") (class "Default")
      (node (ref "U4") (pin "15") (pinfunction "D12_15") (pintype "unspecified"))
    )
    (net (code "166") (name "unconnected-(U4-D13-Pad16)") (class "Default")
      (node (ref "U4") (pin "16") (pinfunction "D13_16") (pintype "unspecified"))
    )
    (net (code "167") (name "unconnected-(U4-GND-Pad4)") (class "Default")
      (node (ref "U4") (pin "4") (pinfunction "GND_4") (pintype "unspecified"))
    )
    (net (code "168") (name "unconnected-(U4-GND-Pad29)") (class "Default")
      (node (ref "U4") (pin "29") (pinfunction "GND_29") (pintype "unspecified"))
    )
    (net (code "169") (name "unconnected-(U4-RESET-Pad3)") (class "Default")
      (node (ref "U4") (pin "3") (pinfunction "RESET_3") (pintype "unspecified"))
    )
    (net (code "170") (name "unconnected-(U4-RESET-Pad28)") (class "Default")
      (node (ref "U4") (pin "28") (pinfunction "RESET_28") (pintype "unspecified"))
    )
    (net (code "171") (name "unconnected-(U4-VIN-Pad30)") (class "Default")
      (node (ref "U4") (pin "30") (pinfunction "VIN_30") (pintype "unspecified"))
    )
    (net (code "172") (name "unconnected-(U5-3Vo-Pad2)") (class "Default")
      (node (ref "U5") (pin "2") (pinfunction "3Vo_2") (pintype "unspecified"))
    )
    (net (code "173") (name "unconnected-(U5-cs-Pad7)") (class "Default")
      (node (ref "U5") (pin "7") (pinfunction "cs_7") (pintype "unspecified"))
    )
    (net (code "174") (name "unconnected-(U5-int-Pad8)") (class "Default")
      (node (ref "U5") (pin "8") (pinfunction "int_8") (pintype "unspecified"))
    )
    (net (code "175") (name "unconnected-(U5-sdo-Pad5)") (class "Default")
      (node (ref "U5") (pin "5") (pinfunction "sdo_5") (pintype "unspecified"))
    )
    (net (code "176") (name "unconnected-(U6-Pad3vo)") (class "Default")
      (node (ref "U6") (pin "3vo") (pinfunction "3vo_3vo") (pintype "unspecified"))
    )
    (net (code "177") (name "unconnected-(U6-PadADR)") (class "Default")
      (node (ref "U6") (pin "ADR") (pinfunction "ADR_ADR") (pintype "unspecified"))
    )
    (net (code "178") (name "unconnected-(U6-PadINT)") (class "Default")
      (node (ref "U6") (pin "INT") (pinfunction "INT_INT") (pintype "unspecified"))
    )
    (net (code "179") (name "unconnected-(U6-PadPS0)") (class "Default")
      (node (ref "U6") (pin "PS0") (pinfunction "PS0_PS0") (pintype "unspecified"))
    )
    (net (code "180") (name "unconnected-(U6-PadPS1)") (class "Default")
      (node (ref "U6") (pin "PS1") (pinfunction "PS1_PS1") (pintype "unspecified"))
    )
    (net (code "181") (name "unconnected-(U6-PadRST)") (class "Default")
      (node (ref "U6") (pin "RST") (pinfunction "RST_RST") (pintype "unspecified"))
    )
    (net (code "182") (name "unconnected-(U7-3Vo-Pad2)") (class "Default")
      (node (ref "U7") (pin "2") (pinfunction "3Vo_2") (pintype "unspecified"))
    )
    (net (code "183") (name "unconnected-(U7-cs-Pad7)") (class "Default")
      (node (ref "U7") (pin "7") (pinfunction "cs_7") (pintype "unspecified"))
    )
    (net (code "184") (name "unconnected-(U7-int-Pad8)") (class "Default")
      (node (ref "U7") (pin "8") (pinfunction "int_8") (pintype "unspecified"))
    )
    (net (code "185") (name "unconnected-(U7-sdo-Pad5)") (class "Default")
      (node (ref "U7") (pin "5") (pinfunction "sdo_5") (pintype "unspecified"))
    )
    (net (code "186") (name "unconnected-(U10-3V3-Pad17)") (class "Default")
      (node (ref "U10") (pin "17") (pinfunction "3V3_17") (pintype "unspecified"))
    )
    (net (code "187") (name "unconnected-(U10-5V-Pad2)") (class "Default")
      (node (ref "U10") (pin "2") (pinfunction "5V_2") (pintype "unspecified"))
    )
    (net (code "188") (name "unconnected-(U10-5V-Pad4)") (class "Default")
      (node (ref "U10") (pin "4") (pinfunction "5V_4") (pintype "unspecified"))
    )
    (net (code "189") (name "unconnected-(U10-ADC.AIN2-Pad40)") (class "Default")
      (node (ref "U10") (pin "40") (pinfunction "ADC.AIN2_40") (pintype "unspecified"))
    )
    (net (code "190") (name "unconnected-(U10-ADC.AIN3-Pad37)") (class "Default")
      (node (ref "U10") (pin "37") (pinfunction "ADC.AIN3_37") (pintype "unspecified"))
    )
    (net (code "191") (name "unconnected-(U10-GND-Pad9)") (class "Default")
      (node (ref "U10") (pin "9") (pinfunction "GND_9") (pintype "unspecified"))
    )
    (net (code "192") (name "unconnected-(U10-GND-Pad14)") (class "Default")
      (node (ref "U10") (pin "14") (pinfunction "GND_14") (pintype "unspecified"))
    )
    (net (code "193") (name "unconnected-(U10-GND-Pad20)") (class "Default")
      (node (ref "U10") (pin "20") (pinfunction "GND_20") (pintype "unspecified"))
    )
    (net (code "194") (name "unconnected-(U10-GND-Pad25)") (class "Default")
      (node (ref "U10") (pin "25") (pinfunction "GND_25") (pintype "unspecified"))
    )
    (net (code "195") (name "unconnected-(U10-GND-Pad30)") (class "Default")
      (node (ref "U10") (pin "30") (pinfunction "GND_30") (pintype "unspecified"))
    )
    (net (code "196") (name "unconnected-(U10-GND-Pad34)") (class "Default")
      (node (ref "U10") (pin "34") (pinfunction "GND_34") (pintype "unspecified"))
    )
    (net (code "197") (name "unconnected-(U10-GND-Pad39)") (class "Default")
      (node (ref "U10") (pin "39") (pinfunction "GND_39") (pintype "unspecified"))
    )
    (net (code "198") (name "unconnected-(U10-GPIOA_4-Pad26)") (class "Default")
      (node (ref "U10") (pin "26") (pinfunction "GPIOA_4_26") (pintype "unspecified"))
    )
    (net (code "199") (name "unconnected-(U10-GPIOA_12-Pad32)") (class "Default")
      (node (ref "U10") (pin "32") (pinfunction "GPIOA_12_32") (pintype "unspecified"))
    )
    (net (code "200") (name "unconnected-(U10-GPIOX_0-Pad16)") (class "Default")
      (node (ref "U10") (pin "16") (pinfunction "GPIOX_0_16") (pintype "unspecified"))
    )
    (net (code "201") (name "unconnected-(U10-GPIOX_1-Pad18)") (class "Default")
      (node (ref "U10") (pin "18") (pinfunction "GPIOX_1_18") (pintype "unspecified"))
    )
    (net (code "202") (name "unconnected-(U10-GPIOX_2-Pad22)") (class "Default")
      (node (ref "U10") (pin "22") (pinfunction "GPIOX_2_22") (pintype "unspecified"))
    )
    (net (code "203") (name "unconnected-(U10-GPIOX_4-Pad13)") (class "Default")
      (node (ref "U10") (pin "13") (pinfunction "GPIOX_4_13") (pintype "unspecified"))
    )
    (net (code "204") (name "unconnected-(U10-I2C_M2_SCL_{slash}_GPIOX_18-Pad5)") (class "Default")
      (node (ref "U10") (pin "5") (pinfunction "I2C_M2_SCL_/_GPIOX_18_5") (pintype "unspecified"))
    )
    (net (code "205") (name "unconnected-(U10-I2C_M2_SDA_{slash}_GPIOX_17-Pad3)") (class "Default")
      (node (ref "U10") (pin "3") (pinfunction "I2C_M2_SDA_/_GPIOX_17_3") (pintype "unspecified"))
    )
    (net (code "206") (name "unconnected-(U10-I2C_M3_SCL_{slash}_GPIOA_15-Pad28)") (class "Default")
      (node (ref "U10") (pin "28") (pinfunction "I2C_M3_SCL_/_GPIOA_15_28") (pintype "unspecified"))
    )
    (net (code "207") (name "unconnected-(U10-I2C_M3_SDA_{slash}_GPIOA_14-Pad27)") (class "Default")
      (node (ref "U10") (pin "27") (pinfunction "I2C_M3_SDA_/_GPIOA_14_27") (pintype "unspecified"))
    )
    (net (code "208") (name "unconnected-(U10-PWM_B_{slash}_GPIOX_19-Pad36)") (class "Default")
      (node (ref "U10") (pin "36") (pinfunction "PWM_B_/_GPIOX_19_36") (pintype "unspecified"))
    )
    (net (code "209") (name "unconnected-(U10-PWM_B_{slash}_PWM_F_{slash}_GPIOX_7-Pad15)") (class "Default")
      (node (ref "U10") (pin "15") (pinfunction "PWM_B_/_PWM_F_/_GPIOX_7_15") (pintype "unspecified"))
    )
    (net (code "210") (name "unconnected-(U10-PWM_C_{slash}_GPIOX_5-Pad33)") (class "Default")
      (node (ref "U10") (pin "33") (pinfunction "PWM_C_/_GPIOX_5_33") (pintype "unspecified"))
    )
    (net (code "211") (name "unconnected-(U10-PWM_D_{slash}_GPIOX_3-Pad11)") (class "Default")
      (node (ref "U10") (pin "11") (pinfunction "PWM_D_/_GPIOX_3_11") (pintype "unspecified"))
    )
    (net (code "212") (name "unconnected-(U10-PWM_D_{slash}_GPIOX_6-Pad35)") (class "Default")
      (node (ref "U10") (pin "35") (pinfunction "PWM_D_/_GPIOX_6_35") (pintype "unspecified"))
    )
    (net (code "213") (name "unconnected-(U10-PWM_E_{slash}_GPIOX_16-Pad12)") (class "Default")
      (node (ref "U10") (pin "12") (pinfunction "PWM_E_/_GPIOX_16_12") (pintype "unspecified"))
    )
    (net (code "214") (name "unconnected-(U10-SPDIF_OUT_{slash}_GPIOA_13-Pad7)") (class "Default")
      (node (ref "U10") (pin "7") (pinfunction "SPDIF_OUT_/_GPIOA_13_7") (pintype "unspecified"))
    )
    (net (code "215") (name "unconnected-(U10-SPI_MISO_{slash}_GPIOX_9-Pad21)") (class "Default")
      (node (ref "U10") (pin "21") (pinfunction "SPI_MISO_/_GPIOX_9_21") (pintype "unspecified"))
    )
    (net (code "216") (name "unconnected-(U10-SPI_MOSI_{slash}_GPIOX_8-Pad19)") (class "Default")
      (node (ref "U10") (pin "19") (pinfunction "SPI_MOSI_/_GPIOX_8_19") (pintype "unspecified"))
    )
    (net (code "217") (name "unconnected-(U10-SPI_SCLK_{slash}_GPIOX_11-Pad23)") (class "Default")
      (node (ref "U10") (pin "23") (pinfunction "SPI_SCLK_/_GPIOX_11_23") (pintype "unspecified"))
    )
    (net (code "218") (name "unconnected-(U10-SPI_SS0_{slash}_GPIOX_10-Pad24)") (class "Default")
      (node (ref "U10") (pin "24") (pinfunction "SPI_SS0_/_GPIOX_10_24") (pintype "unspecified"))
    )
    (net (code "219") (name "unconnected-(U10-UART_CTS_{slash}_GPIOX_14-Pad29)") (class "Default")
      (node (ref "U10") (pin "29") (pinfunction "UART_CTS_/_GPIOX_14_29") (pintype "unspecified"))
    )
    (net (code "220") (name "unconnected-(U10-UART_RTS_{slash}_GPIOX_15-Pad31)") (class "Default")
      (node (ref "U10") (pin "31") (pinfunction "UART_RTS_/_GPIOX_15_31") (pintype "unspecified"))
    )
    (net (code "221") (name "unconnected-(U10-VDDIO_AO1V8-Pad38)") (class "Default")
      (node (ref "U10") (pin "38") (pinfunction "VDDIO_AO1V8_38") (pintype "unspecified"))
    )
  )
)
